# Buck_Converter_Sch.net
KiCad netlist of a schematic drawn in Altium Designer
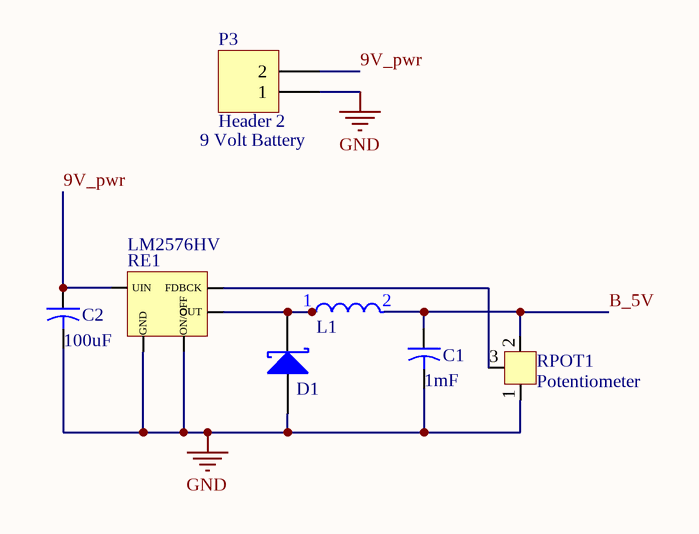
[diagram p0: Buck_Converter Sch.SchDoc]

(export (version "E")
  (design (tool "Eeschema 10.0.6"))
  (components
    (comp (ref "C1")
      (value "1mF")
      (footprint "CAPR5-4X5")
      (description "Capacitor")
      (fields (field (name "Comment") "Cap2") (field (name "PUBLISHER") "Altium Limited"))
      (libsource (lib "Miscellaneous Devices") (part "Cap2"))
    )
    (comp (ref "C2")
      (value "100uF")
      (footprint "CAPR5-4X5")
      (description "Capacitor")
      (fields (field (name "Comment") "Cap2") (field (name "PUBLISHER") "Altium Limited"))
      (libsource (lib "Miscellaneous Devices") (part "Cap2"))
    )
    (comp (ref "D1")
      (value "Diode 11DQ03")
      (footprint "DO-204AL")
      (description "Schottky Rectifier")
      (fields (field (name "PUBLISHER") "Altium Limited"))
      (libsource (lib "Miscellaneous Devices") (part "Diode 11DQ03"))
    )
    (comp (ref "L1")
      (value "Inductor SMD 100 uH")
      (footprint "Inductor 100uH")
      (libsource (lib "Symbols") (part "Inductor SMD 100 uH"))
    )
    (comp (ref "P3")
      (value "Header 2")
      (footprint "HDR1X2")
      (description "Header, 2-Pin")
      (fields (field (name "PUBLISHER") "Altium Limited"))
      (libsource (lib "Miscellaneous Connectors") (part "Header 2"))
    )
    (comp (ref "RE1") (value "LM2576HV") (footprint "LM2576") (libsource (lib "Symbols") (part "LM2576HV")))
    (comp (ref "RPOT1")
      (value "Potentiometer")
      (footprint "Potentiometer 10k")
      (description "potentiometer 10k")
      (libsource (lib "Symbols") (part "Potentiometer"))
    )
  )
  (nets
    (net (code "1") (name "/9V_pwr") (class "Default")
      (node (ref "C2") (pin "1") (pinfunction "1_1") (pintype "passive"))
      (node (ref "P3") (pin "2") (pinfunction "2_2") (pintype "passive"))
      (node (ref "RE1") (pin "1") (pinfunction "UIN_1") (pintype "passive"))
    )
    (net (code "2") (name "/B_5V") (class "Default")
      (node (ref "C1") (pin "1") (pinfunction "1_1") (pintype "passive"))
      (node (ref "L1") (pin "2") (pinfunction "2_2") (pintype "passive"))
      (node (ref "RPOT1") (pin "2") (pinfunction "2_2") (pintype "passive"))
    )
    (net (code "3") (name "GND") (class "Default")
      (node (ref "C1") (pin "2") (pinfunction "2_2") (pintype "passive"))
      (node (ref "C2") (pin "2") (pinfunction "2_2") (pintype "passive"))
      (node (ref "D1") (pin "1") (pinfunction "A_1") (pintype "passive"))
      (node (ref "P3") (pin "1") (pinfunction "1_1") (pintype "passive"))
      (node (ref "RE1") (pin "3") (pinfunction "GND_3") (pintype "passive"))
      (node (ref "RE1") (pin "5") (pinfunction "ON/OFF_5") (pintype "passive"))
      (node (ref "RPOT1") (pin "1") (pinfunction "1_1") (pintype "passive"))
    )
    (net (code "4") (name "Net-(D1-K)") (class "Default")
      (node (ref "D1") (pin "2") (pinfunction "K_2") (pintype "passive"))
      (node (ref "L1") (pin "1") (pinfunction "1_1") (pintype "passive"))
      (node (ref "RE1") (pin "2") (pinfunction "OUT_2") (pintype "passive"))
    )
    (net (code "5") (name "Net-(RE1-FDBCK)") (class "Default")
      (node (ref "RE1") (pin "4") (pinfunction "FDBCK_4") (pintype "passive"))
      (node (ref "RPOT1") (pin "3") (pinfunction "3_3") (pintype "passive"))
    )
  )
)
